# shifter_test.net
KiCad netlist of a schematic drawn in EAGLE
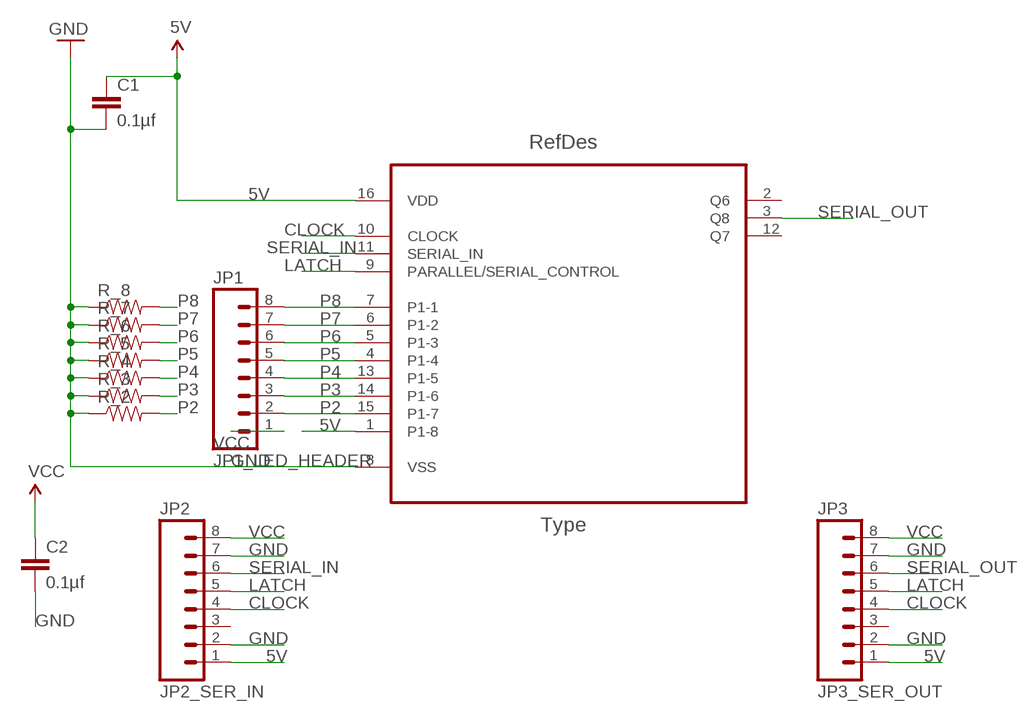
[diagram p0: schematic, sheet 1]

(export (version "E")
  (design (tool "Eeschema 10.0.6"))
  (components
    (comp (ref "C1")
      (value "0.1µf")
      (footprint "eagle-import:CAP-PTH-SMALL2")
      (libsource (lib "eagle-import") (part "CAPPTH2"))
    )
    (comp (ref "C2")
      (value "0.1µf")
      (footprint "eagle-import:CAP-PTH-SMALL2")
      (libsource (lib "eagle-import") (part "CAPPTH2"))
    )
    (comp (ref "JP1")
      (value "JP1_LED_HEADER")
      (footprint "eagle-import:1X08")
      (libsource (lib "eagle-import") (part "M081X08"))
    )
    (comp (ref "JP2")
      (value "JP2_SER_IN")
      (footprint "eagle-import:1X08")
      (libsource (lib "eagle-import") (part "M081X08"))
    )
    (comp (ref "JP3")
      (value "JP3_SER_OUT")
      (footprint "eagle-import:1X08")
      (libsource (lib "eagle-import") (part "M081X08"))
    )
    (comp (ref "R_2")
      (value "RESISTORAXIAL-0.3")
      (footprint "eagle-import:AXIAL-0.3")
      (libsource (lib "eagle-import") (part "RESISTORAXIAL-0.3"))
    )
    (comp (ref "R_3")
      (value "RESISTORAXIAL-0.3")
      (footprint "eagle-import:AXIAL-0.3")
      (libsource (lib "eagle-import") (part "RESISTORAXIAL-0.3"))
    )
    (comp (ref "R_4")
      (value "RESISTORAXIAL-0.3")
      (footprint "eagle-import:AXIAL-0.3")
      (libsource (lib "eagle-import") (part "RESISTORAXIAL-0.3"))
    )
    (comp (ref "R_5")
      (value "RESISTORAXIAL-0.3")
      (footprint "eagle-import:AXIAL-0.3")
      (libsource (lib "eagle-import") (part "RESISTORAXIAL-0.3"))
    )
    (comp (ref "R_6")
      (value "RESISTORAXIAL-0.3")
      (footprint "eagle-import:AXIAL-0.3")
      (libsource (lib "eagle-import") (part "RESISTORAXIAL-0.3"))
    )
    (comp (ref "R_7")
      (value "RESISTORAXIAL-0.3")
      (footprint "eagle-import:AXIAL-0.3")
      (libsource (lib "eagle-import") (part "RESISTORAXIAL-0.3"))
    )
    (comp (ref "R_8")
      (value "RESISTORAXIAL-0.3")
      (footprint "eagle-import:AXIAL-0.3")
      (libsource (lib "eagle-import") (part "RESISTORAXIAL-0.3"))
    )
    (comp (ref "U1")
      (value "CD4021BE")
      (footprint "eagle-import:DIP254P762X508-16")
      (libsource (lib "eagle-import") (part "CD4021BE"))
    )
  )
  (nets
    (net (code "1") (name "/CLOCK") (class "Default")
      (node (ref "JP2") (pin "4") (pinfunction "4_4") (pintype "passive"))
      (node (ref "JP3") (pin "4") (pinfunction "4_4") (pintype "passive"))
      (node (ref "U1") (pin "10") (pinfunction "CLOCK_10") (pintype "input"))
    )
    (net (code "2") (name "/LATCH") (class "Default")
      (node (ref "JP2") (pin "5") (pinfunction "5_5") (pintype "passive"))
      (node (ref "JP3") (pin "5") (pinfunction "5_5") (pintype "passive"))
      (node (ref "U1") (pin "9") (pinfunction "PARALLEL/SERIAL_CONTROL_9") (pintype "input"))
    )
    (net (code "3") (name "/P2") (class "Default")
      (node (ref "JP1") (pin "2") (pinfunction "2_2") (pintype "passive"))
      (node (ref "R_2") (pin "P$2") (pinfunction "2_P$2") (pintype "passive"))
      (node (ref "U1") (pin "15") (pinfunction "P1-7_15") (pintype "input"))
    )
    (net (code "4") (name "/P3") (class "Default")
      (node (ref "JP1") (pin "3") (pinfunction "3_3") (pintype "passive"))
      (node (ref "R_3") (pin "P$2") (pinfunction "2_P$2") (pintype "passive"))
      (node (ref "U1") (pin "14") (pinfunction "P1-6_14") (pintype "input"))
    )
    (net (code "5") (name "/P4") (class "Default")
      (node (ref "JP1") (pin "4") (pinfunction "4_4") (pintype "passive"))
      (node (ref "R_4") (pin "P$2") (pinfunction "2_P$2") (pintype "passive"))
      (node (ref "U1") (pin "13") (pinfunction "P1-5_13") (pintype "input"))
    )
    (net (code "6") (name "/P5") (class "Default")
      (node (ref "JP1") (pin "5") (pinfunction "5_5") (pintype "passive"))
      (node (ref "R_5") (pin "P$2") (pinfunction "2_P$2") (pintype "passive"))
      (node (ref "U1") (pin "4") (pinfunction "P1-4_4") (pintype "input"))
    )
    (net (code "7") (name "/P6") (class "Default")
      (node (ref "JP1") (pin "6") (pinfunction "6_6") (pintype "passive"))
      (node (ref "R_6") (pin "P$2") (pinfunction "2_P$2") (pintype "passive"))
      (node (ref "U1") (pin "5") (pinfunction "P1-3_5") (pintype "input"))
    )
    (net (code "8") (name "/P7") (class "Default")
      (node (ref "JP1") (pin "7") (pinfunction "7_7") (pintype "passive"))
      (node (ref "R_7") (pin "P$2") (pinfunction "2_P$2") (pintype "passive"))
      (node (ref "U1") (pin "6") (pinfunction "P1-2_6") (pintype "input"))
    )
    (net (code "9") (name "/P8") (class "Default")
      (node (ref "JP1") (pin "8") (pinfunction "8_8") (pintype "passive"))
      (node (ref "R_8") (pin "P$2") (pinfunction "2_P$2") (pintype "passive"))
      (node (ref "U1") (pin "7") (pinfunction "P1-1_7") (pintype "input"))
    )
    (net (code "10") (name "/SERIAL_IN") (class "Default")
      (node (ref "JP2") (pin "6") (pinfunction "6_6") (pintype "passive"))
      (node (ref "U1") (pin "11") (pinfunction "SERIAL_IN_11") (pintype "input"))
    )
    (net (code "11") (name "/SERIAL_OUT") (class "Default")
      (node (ref "JP3") (pin "6") (pinfunction "6_6") (pintype "passive"))
      (node (ref "U1") (pin "3") (pinfunction "Q8_3") (pintype "output"))
    )
    (net (code "12") (name "5V") (class "Default")
      (node (ref "C1") (pin "1") (pinfunction "1_1") (pintype "passive"))
      (node (ref "JP2") (pin "1") (pinfunction "1_1") (pintype "passive"))
      (node (ref "JP3") (pin "1") (pinfunction "1_1") (pintype "passive"))
      (node (ref "U1") (pin "1") (pinfunction "P1-8_1") (pintype "input"))
      (node (ref "U1") (pin "16") (pinfunction "VDD_16") (pintype "power_in"))
    )
    (net (code "13") (name "GND") (class "Default")
      (node (ref "C1") (pin "2") (pinfunction "2_2") (pintype "passive"))
      (node (ref "C2") (pin "2") (pinfunction "2_2") (pintype "passive"))
      (node (ref "JP2") (pin "2") (pinfunction "2_2") (pintype "passive"))
      (node (ref "JP2") (pin "7") (pinfunction "7_7") (pintype "passive"))
      (node (ref "JP3") (pin "2") (pinfunction "2_2") (pintype "passive"))
      (node (ref "JP3") (pin "7") (pinfunction "7_7") (pintype "passive"))
      (node (ref "R_2") (pin "P$1") (pinfunction "1_P$1") (pintype "passive"))
      (node (ref "R_3") (pin "P$1") (pinfunction "1_P$1") (pintype "passive"))
      (node (ref "R_4") (pin "P$1") (pinfunction "1_P$1") (pintype "passive"))
      (node (ref "R_5") (pin "P$1") (pinfunction "1_P$1") (pintype "passive"))
      (node (ref "R_6") (pin "P$1") (pinfunction "1_P$1") (pintype "passive"))
      (node (ref "R_7") (pin "P$1") (pinfunction "1_P$1") (pintype "passive"))
      (node (ref "R_8") (pin "P$1") (pinfunction "1_P$1") (pintype "passive"))
      (node (ref "U1") (pin "8") (pinfunction "VSS_8") (pintype "passive"))
    )
    (net (code "14") (name "VCC") (class "Default")
      (node (ref "C2") (pin "1") (pinfunction "1_1") (pintype "passive"))
      (node (ref "JP1") (pin "1") (pinfunction "1_1") (pintype "passive"))
      (node (ref "JP2") (pin "8") (pinfunction "8_8") (pintype "passive"))
      (node (ref "JP3") (pin "8") (pinfunction "8_8") (pintype "passive"))
    )
    (net (code "15") (name "unconnected-(JP2-Pad3)") (class "Default")
      (node (ref "JP2") (pin "3") (pinfunction "3_3") (pintype "passive"))
    )
    (net (code "16") (name "unconnected-(JP3-Pad3)") (class "Default")
      (node (ref "JP3") (pin "3") (pinfunction "3_3") (pintype "passive"))
    )
    (net (code "17") (name "unconnected-(U1-Q6-Pad2)") (class "Default")
      (node (ref "U1") (pin "2") (pinfunction "Q6_2") (pintype "output"))
    )
    (net (code "18") (name "unconnected-(U1-Q7-Pad12)") (class "Default")
      (node (ref "U1") (pin "12") (pinfunction "Q7_12") (pintype "output"))
    )
  )
)
